# 80PIN_FMU3_REV_G.net
KiCad netlist of a schematic drawn in Altium Designer
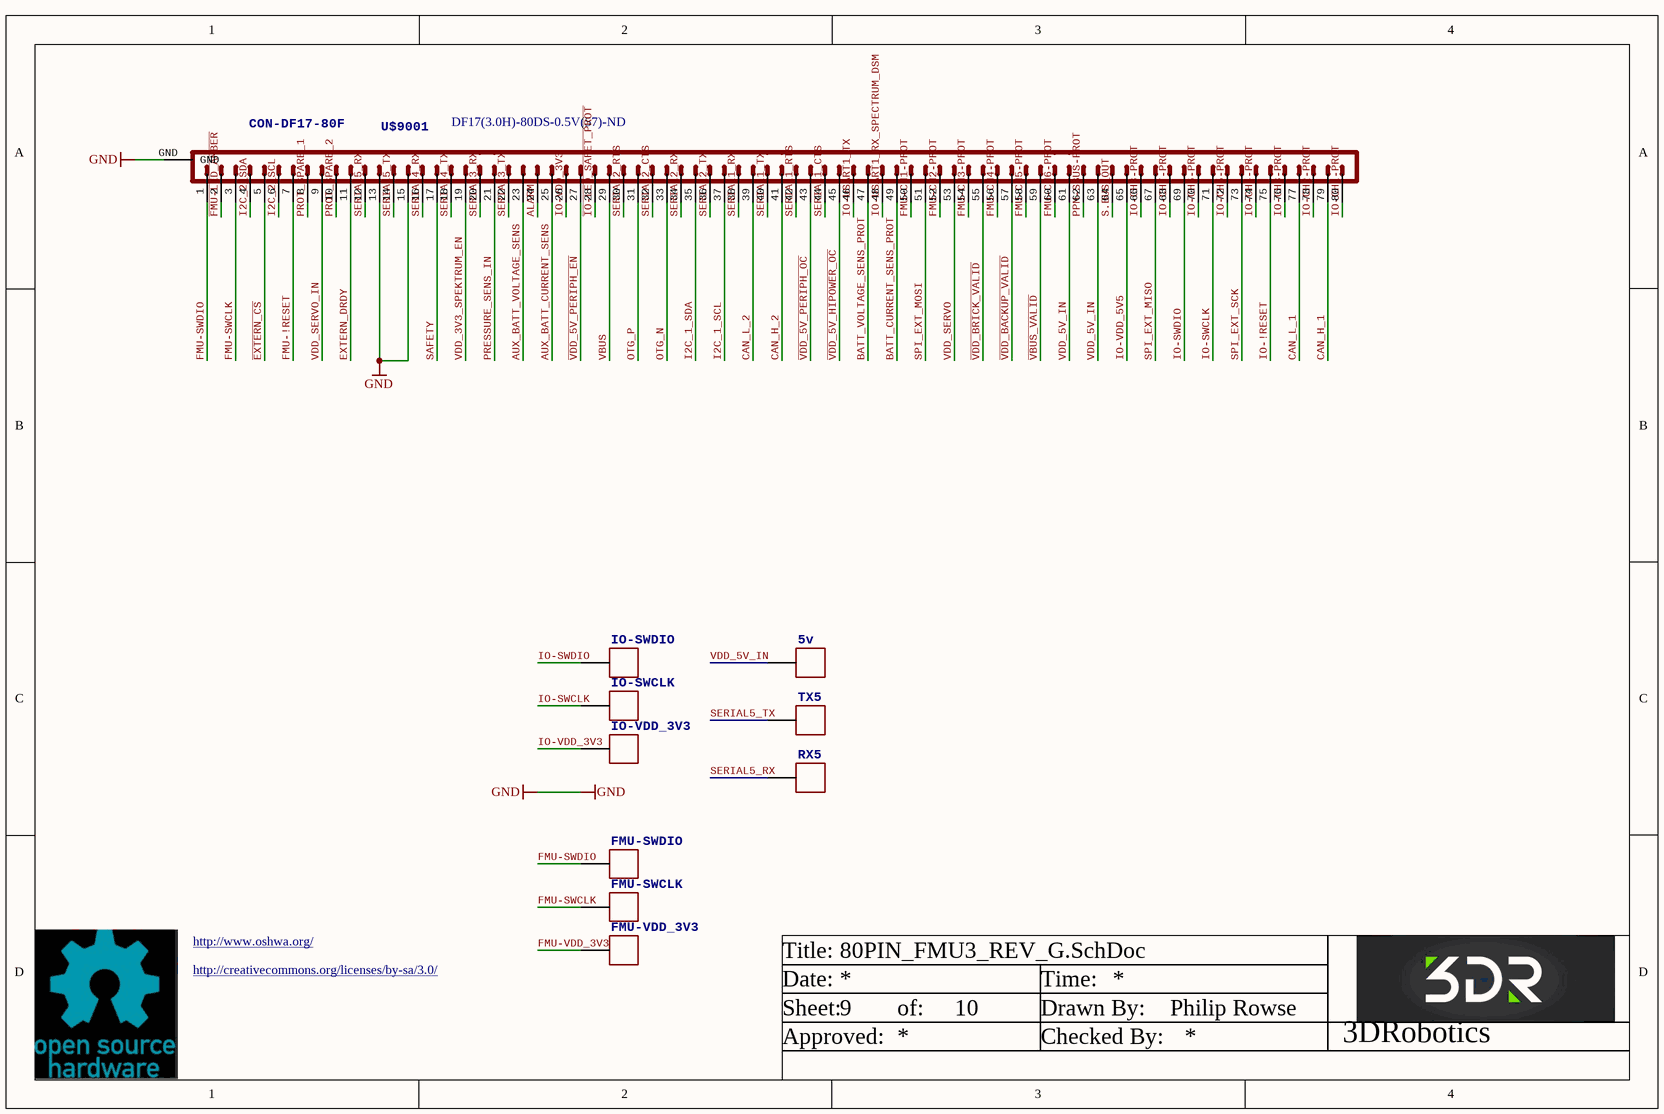
[diagram p0: 80PIN_FMU3_REV_G.SchDoc]

(export (version "E")
  (design (tool "Eeschema 10.0.6"))
  (components
    (comp (ref "5v") (value "PAD.04") (footprint "PAD.04X.04") (libsource (lib "pixhawk2") (part "PAD.04")))
    (comp (ref "FMU-SWCLK")
      (value "PAD.04")
      (footprint "PAD.04X.04")
      (libsource (lib "pixhawk2") (part "PAD.04"))
    )
    (comp (ref "FMU-SWDIO")
      (value "PAD.04")
      (footprint "PAD.04X.04")
      (libsource (lib "pixhawk2") (part "PAD.04"))
    )
    (comp (ref "FMU-VDD_3V3")
      (value "PAD.04")
      (footprint "PAD.04X.04")
      (libsource (lib "pixhawk2") (part "PAD.04"))
    )
    (comp (ref "IO-SWCLK")
      (value "PAD.04")
      (footprint "PAD.04X.04")
      (libsource (lib "pixhawk2") (part "PAD.04"))
    )
    (comp (ref "IO-SWDIO")
      (value "PAD.04")
      (footprint "PAD.04X.04")
      (libsource (lib "pixhawk2") (part "PAD.04"))
    )
    (comp (ref "IO-VDD_3V3")
      (value "PAD.04")
      (footprint "PAD.04X.04")
      (libsource (lib "pixhawk2") (part "PAD.04"))
    )
    (comp (ref "RX5") (value "PAD.04") (footprint "PAD.04X.04") (libsource (lib "pixhawk2") (part "PAD.04")))
    (comp (ref "TX5") (value "PAD.04") (footprint "PAD.04X.04") (libsource (lib "pixhawk2") (part "PAD.04")))
    (comp (ref "U$9001")
      (value "CON-DF17-80F")
      (footprint "CON-DF17-80F")
      (description "CONN RECEPT 80POS .5MM SMD W/FIT")
      (fields
        (field (name "SUPPLIER PART NUMBER 1") "DF17(3.0H)-80DS-0.5V(57)-ND")
        (field (name "3DR_PARTNO") "ECM0518")
        (field (name "PARTNO") "DF17(3.0H)-80DS-0.5V(57)")
      )
      (libsource (lib "pixhawk2") (part "CON-DF17-80F"))
    )
  )
  (nets
    (net (code "1") (name "/ALARM") (class "Default")
      (node (ref "U$9001") (pin "24") (pinfunction "24_24") (pintype "passive"))
    )
    (net (code "2") (name "/AUX_BATT_CURRENT_SENS") (class "Default")
      (node (ref "U$9001") (pin "25") (pinfunction "25_25") (pintype "passive"))
    )
    (net (code "3") (name "/AUX_BATT_VOLTAGE_SENS") (class "Default")
      (node (ref "U$9001") (pin "23") (pinfunction "23_23") (pintype "passive"))
    )
    (net (code "4") (name "/BATT_CURRENT_SENS_PROT") (class "Default")
      (node (ref "U$9001") (pin "49") (pinfunction "49_49") (pintype "passive"))
    )
    (net (code "5") (name "/BATT_VOLTAGE_SENS_PROT") (class "Default")
      (node (ref "U$9001") (pin "47") (pinfunction "47_47") (pintype "passive"))
    )
    (net (code "6") (name "/CAN_H_1") (class "Default")
      (node (ref "U$9001") (pin "79") (pinfunction "79_79") (pintype "passive"))
    )
    (net (code "7") (name "/CAN_H_2") (class "Default")
      (node (ref "U$9001") (pin "41") (pinfunction "41_41") (pintype "passive"))
    )
    (net (code "8") (name "/CAN_L_1") (class "Default")
      (node (ref "U$9001") (pin "77") (pinfunction "77_77") (pintype "passive"))
    )
    (net (code "9") (name "/CAN_L_2") (class "Default")
      (node (ref "U$9001") (pin "39") (pinfunction "39_39") (pintype "passive"))
    )
    (net (code "10") (name "/EXTERN_DRDY") (class "Default")
      (node (ref "U$9001") (pin "11") (pinfunction "11_11") (pintype "passive"))
    )
    (net (code "11") (name "/FMU-!RESET") (class "Default")
      (node (ref "U$9001") (pin "7") (pinfunction "7_7") (pintype "passive"))
    )
    (net (code "12") (name "/FMU-CH1-PROT") (class "Default")
      (node (ref "U$9001") (pin "50") (pinfunction "50_50") (pintype "passive"))
    )
    (net (code "13") (name "/FMU-CH2-PROT") (class "Default")
      (node (ref "U$9001") (pin "52") (pinfunction "52_52") (pintype "passive"))
    )
    (net (code "14") (name "/FMU-CH3-PROT") (class "Default")
      (node (ref "U$9001") (pin "54") (pinfunction "54_54") (pintype "passive"))
    )
    (net (code "15") (name "/FMU-CH4-PROT") (class "Default")
      (node (ref "U$9001") (pin "56") (pinfunction "56_56") (pintype "passive"))
    )
    (net (code "16") (name "/FMU-CH5-PROT") (class "Default")
      (node (ref "U$9001") (pin "58") (pinfunction "58_58") (pintype "passive"))
    )
    (net (code "17") (name "/FMU-CH6-PROT") (class "Default")
      (node (ref "U$9001") (pin "60") (pinfunction "60_60") (pintype "passive"))
    )
    (net (code "18") (name "/FMU-SWCLK") (class "Default")
      (node (ref "FMU-SWCLK") (pin "P$1") (pinfunction "P$1_P$1") (pintype "passive"))
      (node (ref "U$9001") (pin "3") (pinfunction "3_3") (pintype "passive"))
    )
    (net (code "19") (name "/FMU-SWDIO") (class "Default")
      (node (ref "FMU-SWDIO") (pin "P$1") (pinfunction "P$1_P$1") (pintype "passive"))
      (node (ref "U$9001") (pin "1") (pinfunction "1_1") (pintype "passive"))
    )
    (net (code "20") (name "/FMU-VDD_3V3") (class "Default")
      (node (ref "FMU-VDD_3V3") (pin "P$1") (pinfunction "P$1_P$1") (pintype "passive"))
    )
    (net (code "21") (name "/I2C_1_SCL") (class "Default")
      (node (ref "U$9001") (pin "37") (pinfunction "37_37") (pintype "passive"))
    )
    (net (code "22") (name "/I2C_1_SDA") (class "Default")
      (node (ref "U$9001") (pin "35") (pinfunction "35_35") (pintype "passive"))
    )
    (net (code "23") (name "/I2C_2_SCL") (class "Default")
      (node (ref "U$9001") (pin "6") (pinfunction "6_6") (pintype "passive"))
    )
    (net (code "24") (name "/I2C_2_SDA") (class "Default")
      (node (ref "U$9001") (pin "4") (pinfunction "4_4") (pintype "passive"))
    )
    (net (code "25") (name "/IO-!RESET") (class "Default")
      (node (ref "U$9001") (pin "75") (pinfunction "75_75") (pintype "passive"))
    )
    (net (code "26") (name "/IO-CH1-PROT") (class "Default")
      (node (ref "U$9001") (pin "80") (pinfunction "80_80") (pintype "passive"))
    )
    (net (code "27") (name "/IO-CH2-PROT") (class "Default")
      (node (ref "U$9001") (pin "78") (pinfunction "78_78") (pintype "passive"))
    )
    (net (code "28") (name "/IO-CH3-PROT") (class "Default")
      (node (ref "U$9001") (pin "76") (pinfunction "76_76") (pintype "passive"))
    )
    (net (code "29") (name "/IO-CH4-PROT") (class "Default")
      (node (ref "U$9001") (pin "74") (pinfunction "74_74") (pintype "passive"))
    )
    (net (code "30") (name "/IO-CH5-PROT") (class "Default")
      (node (ref "U$9001") (pin "72") (pinfunction "72_72") (pintype "passive"))
    )
    (net (code "31") (name "/IO-CH6-PROT") (class "Default")
      (node (ref "U$9001") (pin "70") (pinfunction "70_70") (pintype "passive"))
    )
    (net (code "32") (name "/IO-CH7-PROT") (class "Default")
      (node (ref "U$9001") (pin "68") (pinfunction "68_68") (pintype "passive"))
    )
    (net (code "33") (name "/IO-CH8-PROT") (class "Default")
      (node (ref "U$9001") (pin "66") (pinfunction "66_66") (pintype "passive"))
    )
    (net (code "34") (name "/IO-SWCLK") (class "Default")
      (node (ref "IO-SWCLK") (pin "P$1") (pinfunction "P$1_P$1") (pintype "passive"))
      (node (ref "U$9001") (pin "71") (pinfunction "71_71") (pintype "passive"))
    )
    (net (code "35") (name "/IO-SWDIO") (class "Default")
      (node (ref "IO-SWDIO") (pin "P$1") (pinfunction "P$1_P$1") (pintype "passive"))
      (node (ref "U$9001") (pin "69") (pinfunction "69_69") (pintype "passive"))
    )
    (net (code "36") (name "/IO-USART1_RX_SPECTRUM_DSM") (class "Default")
      (node (ref "U$9001") (pin "48") (pinfunction "48_48") (pintype "passive"))
    )
    (net (code "37") (name "/IO-USART1_TX") (class "Default")
      (node (ref "U$9001") (pin "46") (pinfunction "46_46") (pintype "passive"))
    )
    (net (code "38") (name "/IO-VDD_3V3") (class "Default")
      (node (ref "IO-VDD_3V3") (pin "P$1") (pinfunction "P$1_P$1") (pintype "passive"))
      (node (ref "U$9001") (pin "26") (pinfunction "26_26") (pintype "passive"))
    )
    (net (code "39") (name "/IO-VDD_5V5") (class "Default")
      (node (ref "U$9001") (pin "65") (pinfunction "65_65") (pintype "passive"))
    )
    (net (code "40") (name "/OTG_N") (class "Default")
      (node (ref "U$9001") (pin "33") (pinfunction "33_33") (pintype "passive"))
    )
    (net (code "41") (name "/OTG_P") (class "Default")
      (node (ref "U$9001") (pin "31") (pinfunction "31_31") (pintype "passive"))
    )
    (net (code "42") (name "/PPM-SBUS-PROT") (class "Default")
      (node (ref "U$9001") (pin "62") (pinfunction "62_62") (pintype "passive"))
    )
    (net (code "43") (name "/PRESSURE_SENS_IN") (class "Default")
      (node (ref "U$9001") (pin "21") (pinfunction "21_21") (pintype "passive"))
    )
    (net (code "44") (name "/PROT_SPARE_1") (class "Default")
      (node (ref "U$9001") (pin "8") (pinfunction "8_8") (pintype "passive"))
    )
    (net (code "45") (name "/PROT_SPARE_2") (class "Default")
      (node (ref "U$9001") (pin "10") (pinfunction "10_10") (pintype "passive"))
    )
    (net (code "46") (name "/S.BUS_OUT") (class "Default")
      (node (ref "U$9001") (pin "64") (pinfunction "64_64") (pintype "passive"))
    )
    (net (code "47") (name "/SAFETY") (class "Default")
      (node (ref "U$9001") (pin "17") (pinfunction "17_17") (pintype "passive"))
    )
    (net (code "48") (name "/SERIAL1_CTS") (class "Default")
      (node (ref "U$9001") (pin "44") (pinfunction "44_44") (pintype "passive"))
    )
    (net (code "49") (name "/SERIAL1_RTS") (class "Default")
      (node (ref "U$9001") (pin "42") (pinfunction "42_42") (pintype "passive"))
    )
    (net (code "50") (name "/SERIAL1_RX") (class "Default")
      (node (ref "U$9001") (pin "38") (pinfunction "38_38") (pintype "passive"))
    )
    (net (code "51") (name "/SERIAL1_TX") (class "Default")
      (node (ref "U$9001") (pin "40") (pinfunction "40_40") (pintype "passive"))
    )
    (net (code "52") (name "/SERIAL2_CTS") (class "Default")
      (node (ref "U$9001") (pin "32") (pinfunction "32_32") (pintype "passive"))
    )
    (net (code "53") (name "/SERIAL2_RTS") (class "Default")
      (node (ref "U$9001") (pin "30") (pinfunction "30_30") (pintype "passive"))
    )
    (net (code "54") (name "/SERIAL2_RX") (class "Default")
      (node (ref "U$9001") (pin "34") (pinfunction "34_34") (pintype "passive"))
    )
    (net (code "55") (name "/SERIAL2_TX") (class "Default")
      (node (ref "U$9001") (pin "36") (pinfunction "36_36") (pintype "passive"))
    )
    (net (code "56") (name "/SERIAL3_RX") (class "Default")
      (node (ref "U$9001") (pin "20") (pinfunction "20_20") (pintype "passive"))
    )
    (net (code "57") (name "/SERIAL3_TX") (class "Default")
      (node (ref "U$9001") (pin "22") (pinfunction "22_22") (pintype "passive"))
    )
    (net (code "58") (name "/SERIAL4_RX") (class "Default")
      (node (ref "U$9001") (pin "16") (pinfunction "16_16") (pintype "passive"))
    )
    (net (code "59") (name "/SERIAL4_TX") (class "Default")
      (node (ref "U$9001") (pin "18") (pinfunction "18_18") (pintype "passive"))
    )
    (net (code "60") (name "/SERIAL5_RX") (class "Default")
      (node (ref "RX5") (pin "P$1") (pinfunction "P$1_P$1") (pintype "passive"))
      (node (ref "U$9001") (pin "12") (pinfunction "12_12") (pintype "passive"))
    )
    (net (code "61") (name "/SERIAL5_TX") (class "Default")
      (node (ref "TX5") (pin "P$1") (pinfunction "P$1_P$1") (pintype "passive"))
      (node (ref "U$9001") (pin "14") (pinfunction "14_14") (pintype "passive"))
    )
    (net (code "62") (name "/SPI_EXT_MISO") (class "Default")
      (node (ref "U$9001") (pin "67") (pinfunction "67_67") (pintype "passive"))
    )
    (net (code "63") (name "/SPI_EXT_MOSI") (class "Default")
      (node (ref "U$9001") (pin "51") (pinfunction "51_51") (pintype "passive"))
    )
    (net (code "64") (name "/SPI_EXT_SCK") (class "Default")
      (node (ref "U$9001") (pin "73") (pinfunction "73_73") (pintype "passive"))
    )
    (net (code "65") (name "/VBUS") (class "Default")
      (node (ref "U$9001") (pin "29") (pinfunction "29_29") (pintype "passive"))
    )
    (net (code "66") (name "/VDD_3V3_SPEKTRUM_EN") (class "Default")
      (node (ref "U$9001") (pin "19") (pinfunction "19_19") (pintype "passive"))
    )
    (net (code "67") (name "/VDD_5V_IN") (class "Default")
      (node (ref "5v") (pin "P$1") (pinfunction "P$1_P$1") (pintype "passive"))
      (node (ref "U$9001") (pin "61") (pinfunction "61_61") (pintype "passive"))
      (node (ref "U$9001") (pin "63") (pinfunction "63_63") (pintype "passive"))
    )
    (net (code "68") (name "/VDD_SERVO") (class "Default")
      (node (ref "U$9001") (pin "53") (pinfunction "53_53") (pintype "passive"))
    )
    (net (code "69") (name "/VDD_SERVO_IN") (class "Default")
      (node (ref "U$9001") (pin "9") (pinfunction "9_9") (pintype "passive"))
    )
    (net (code "70") (name "/~{EXTERN_CS}") (class "Default")
      (node (ref "U$9001") (pin "5") (pinfunction "5_5") (pintype "passive"))
    )
    (net (code "71") (name "/~{FMU-LED_AMBER}") (class "Default")
      (node (ref "U$9001") (pin "2") (pinfunction "2_2") (pintype "passive"))
    )
    (net (code "72") (name "/~{IO-LED_SAFET_PROT}") (class "Default")
      (node (ref "U$9001") (pin "28") (pinfunction "28_28") (pintype "passive"))
    )
    (net (code "73") (name "/~{VBUS_VALID}") (class "Default")
      (node (ref "U$9001") (pin "59") (pinfunction "59_59") (pintype "passive"))
    )
    (net (code "74") (name "/~{VDD_5V_HIPOWER_OC}") (class "Default")
      (node (ref "U$9001") (pin "45") (pinfunction "45_45") (pintype "passive"))
    )
    (net (code "75") (name "/~{VDD_5V_PERIPH_EN}") (class "Default")
      (node (ref "U$9001") (pin "27") (pinfunction "27_27") (pintype "passive"))
    )
    (net (code "76") (name "/~{VDD_5V_PERIPH_OC}") (class "Default")
      (node (ref "U$9001") (pin "43") (pinfunction "43_43") (pintype "passive"))
    )
    (net (code "77") (name "/~{VDD_BACKUP_VALID}") (class "Default")
      (node (ref "U$9001") (pin "57") (pinfunction "57_57") (pintype "passive"))
    )
    (net (code "78") (name "/~{VDD_BRICK_VALID}") (class "Default")
      (node (ref "U$9001") (pin "55") (pinfunction "55_55") (pintype "passive"))
    )
    (net (code "79") (name "GND") (class "Default")
      (node (ref "U$9001") (pin "13") (pinfunction "13_13") (pintype "passive"))
      (node (ref "U$9001") (pin "15") (pinfunction "15_15") (pintype "passive"))
      (node (ref "U$9001") (pin "GND") (pinfunction "GND_GND") (pintype "passive"))
    )
  )
)
